# gripper-board-rev1.net
KiCad netlist of a schematic drawn in EAGLE
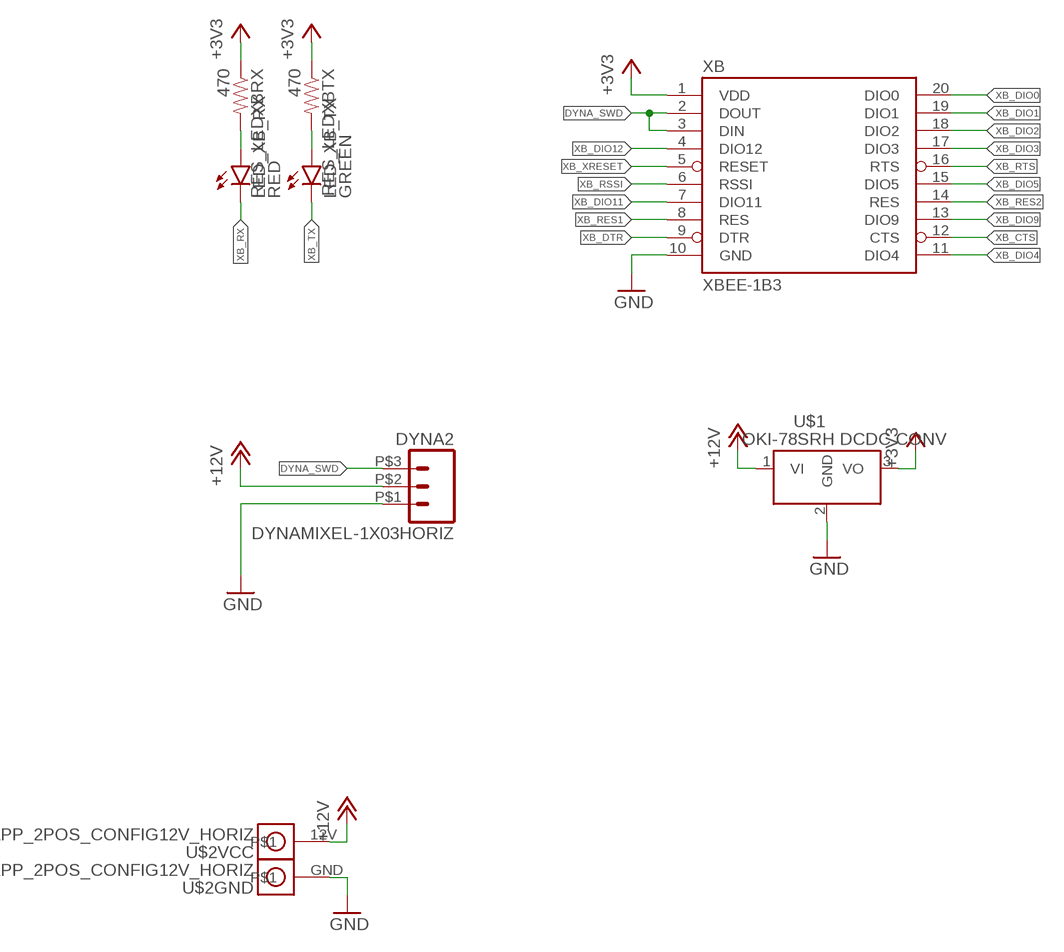
[diagram p0: schematic, sheet 1]

(export (version "E")
  (design (tool "Eeschema 10.0.6"))
  (components
    (comp (ref "DYNA2")
      (value "DYNAMIXEL-1X03HORIZ")
      (footprint "eagle-import:MLX-SPOX5268-3PIN")
      (fields (field (name "MFR") "Molex"))
      (libsource (lib "eagle-import") (part "DYNAMIXEL-1X03HORIZ"))
    )
    (comp (ref "LED_XB_RX")
      (value "RED")
      (footprint "eagle-import:LED-1206")
      (libsource (lib "eagle-import") (part "LED1206"))
    )
    (comp (ref "LED_XB_TX")
      (value "GREEN")
      (footprint "eagle-import:LED-1206")
      (libsource (lib "eagle-import") (part "LED-GREEN1206"))
    )
    (comp (ref "RES_LEDXBRX")
      (value "470")
      (footprint "eagle-import:1206")
      (libsource (lib "eagle-import") (part "RESISTOR1206"))
    )
    (comp (ref "RES_LEDXBTX")
      (value "470")
      (footprint "eagle-import:1206")
      (libsource (lib "eagle-import") (part "RESISTOR1206"))
    )
    (comp (ref "U$1")
      (value "Q_OKI-78SR")
      (footprint "eagle-import:OKI-78SRH")
      (libsource (lib "eagle-import") (part "Q_OKI-78SR"))
    )
    (comp (ref "U$2")
      (value "APP_2POS_CONFIG12V_HORIZ")
      (footprint "eagle-import:APP45_12V_HORIZ_CONFIG")
      (libsource (lib "eagle-import") (part "APP_2POS_CONFIG12V_HORIZ"))
    )
    (comp (ref "XB")
      (value "XBEE-1B3")
      (footprint "eagle-import:XBEE-SMD")
      (libsource (lib "eagle-import") (part "XBEE-1B3"))
    )
  )
  (nets
    (net (code "1") (name "+3V3") (class "Default")
      (node (ref "RES_LEDXBRX") (pin "1") (pinfunction "1_1") (pintype "passive"))
      (node (ref "RES_LEDXBTX") (pin "1") (pinfunction "1_1") (pintype "passive"))
      (node (ref "U$1") (pin "3") (pinfunction "VO_3") (pintype "bidirectional"))
      (node (ref "XB") (pin "1") (pinfunction "VDD_1") (pintype "power_in"))
    )
    (net (code "2") (name "+12V") (class "Default")
      (node (ref "DYNA2") (pin "P$2") (pinfunction "2_P$2") (pintype "passive"))
      (node (ref "U$1") (pin "1") (pinfunction "VI_1") (pintype "bidirectional"))
      (node (ref "U$2") (pin "12V") (pinfunction "P$1_12V") (pintype "bidirectional"))
    )
    (net (code "3") (name "DYNA_SWD") (class "Default")
      (node (ref "DYNA2") (pin "P$3") (pinfunction "3_P$3") (pintype "passive"))
      (node (ref "XB") (pin "2") (pinfunction "DOUT_2") (pintype "output"))
      (node (ref "XB") (pin "3") (pinfunction "DIN_3") (pintype "input"))
    )
    (net (code "4") (name "GND") (class "Default")
      (node (ref "DYNA2") (pin "P$1") (pinfunction "1_P$1") (pintype "passive"))
      (node (ref "U$1") (pin "2") (pinfunction "GND_2") (pintype "bidirectional"))
      (node (ref "U$2") (pin "GND") (pinfunction "P$1_GND") (pintype "bidirectional"))
      (node (ref "XB") (pin "10") (pinfunction "GND_10") (pintype "power_in"))
    )
    (net (code "5") (name "Net-(LED_XB_RX-PadA)") (class "Default")
      (node (ref "LED_XB_RX") (pin "A") (pinfunction "A_A") (pintype "passive"))
      (node (ref "RES_LEDXBRX") (pin "2") (pinfunction "2_2") (pintype "passive"))
    )
    (net (code "6") (name "Net-(LED_XB_TX-PadA)") (class "Default")
      (node (ref "LED_XB_TX") (pin "A") (pinfunction "A_A") (pintype "passive"))
      (node (ref "RES_LEDXBTX") (pin "2") (pinfunction "2_2") (pintype "passive"))
    )
    (net (code "7") (name "XB_CTS") (class "Default")
      (node (ref "XB") (pin "12") (pinfunction "CTS_12") (pintype "output"))
    )
    (net (code "8") (name "XB_DIO0") (class "Default")
      (node (ref "XB") (pin "20") (pinfunction "DIO0_20") (pintype "bidirectional"))
    )
    (net (code "9") (name "XB_DIO1") (class "Default")
      (node (ref "XB") (pin "19") (pinfunction "DIO1_19") (pintype "bidirectional"))
    )
    (net (code "10") (name "XB_DIO2") (class "Default")
      (node (ref "XB") (pin "18") (pinfunction "DIO2_18") (pintype "bidirectional"))
    )
    (net (code "11") (name "XB_DIO3") (class "Default")
      (node (ref "XB") (pin "17") (pinfunction "DIO3_17") (pintype "bidirectional"))
    )
    (net (code "12") (name "XB_DIO4") (class "Default")
      (node (ref "XB") (pin "11") (pinfunction "DIO4_11") (pintype "bidirectional"))
    )
    (net (code "13") (name "XB_DIO5") (class "Default")
      (node (ref "XB") (pin "15") (pinfunction "DIO5_15") (pintype "bidirectional"))
    )
    (net (code "14") (name "XB_DIO9") (class "Default")
      (node (ref "XB") (pin "13") (pinfunction "DIO9_13") (pintype "bidirectional"))
    )
    (net (code "15") (name "XB_DIO11") (class "Default")
      (node (ref "XB") (pin "7") (pinfunction "DIO11_7") (pintype "bidirectional"))
    )
    (net (code "16") (name "XB_DIO12") (class "Default")
      (node (ref "XB") (pin "4") (pinfunction "DIO12_4") (pintype "bidirectional"))
    )
    (net (code "17") (name "XB_DTR") (class "Default")
      (node (ref "XB") (pin "9") (pinfunction "DTR_9") (pintype "bidirectional"))
    )
    (net (code "18") (name "XB_RES1") (class "Default")
      (node (ref "XB") (pin "8") (pinfunction "RES_8") (pintype "bidirectional"))
    )
    (net (code "19") (name "XB_RES2") (class "Default")
      (node (ref "XB") (pin "14") (pinfunction "RES_14") (pintype "bidirectional"))
    )
    (net (code "20") (name "XB_RSSI") (class "Default")
      (node (ref "XB") (pin "6") (pinfunction "RSSI_6") (pintype "bidirectional"))
    )
    (net (code "21") (name "XB_RTS") (class "Default")
      (node (ref "XB") (pin "16") (pinfunction "RTS_16") (pintype "input"))
    )
    (net (code "22") (name "XB_RX") (class "Default")
      (node (ref "LED_XB_RX") (pin "C") (pinfunction "C_C") (pintype "passive"))
    )
    (net (code "23") (name "XB_TX") (class "Default")
      (node (ref "LED_XB_TX") (pin "C") (pinfunction "C_C") (pintype "passive"))
    )
    (net (code "24") (name "XB_XRESET") (class "Default")
      (node (ref "XB") (pin "5") (pinfunction "RESET_5") (pintype "input"))
    )
  )
)
